# ESPRemote.net
KiCad netlist of a schematic drawn in EAGLE
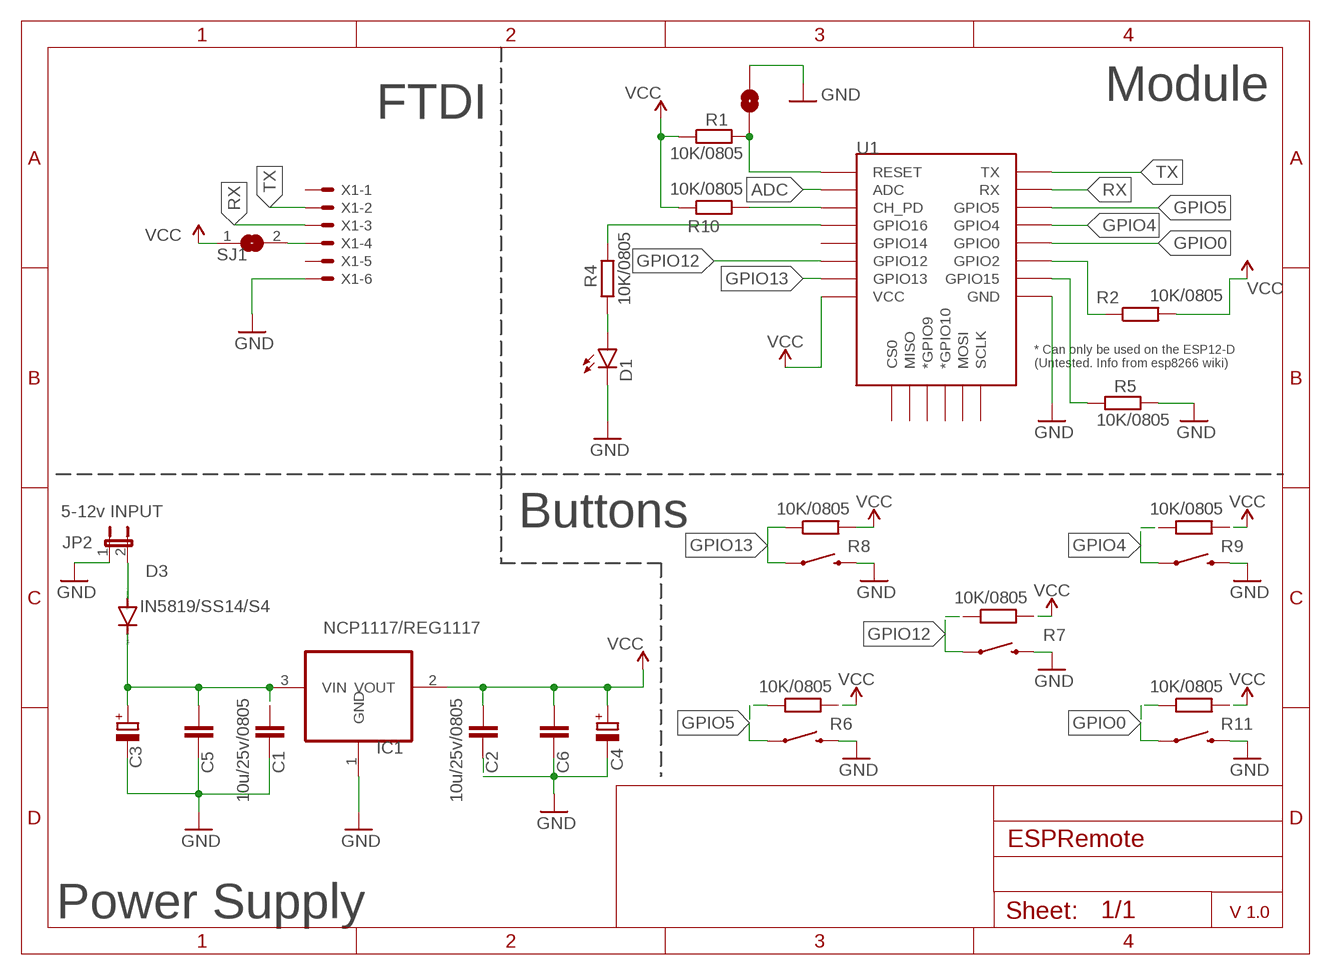
[diagram p0: schematic, sheet 1]

(export (version "E")
  (design (tool "Eeschema 10.0.6"))
  (components
    (comp (ref "C1")
      (value "10u/25v/0805")
      (footprint "eagle-import:C0805")
      (libsource (lib "eagle-import") (part "C-EUC0805"))
    )
    (comp (ref "C2")
      (value "10u/25v/0805")
      (footprint "eagle-import:C0805")
      (libsource (lib "eagle-import") (part "C-EUC0805"))
    )
    (comp (ref "C3")
      (value "CPOL-EUE2-5")
      (footprint "eagle-import:E2-5")
      (libsource (lib "eagle-import") (part "CPOL-EUE2-5"))
    )
    (comp (ref "C4")
      (value "CPOL-EUE2-5")
      (footprint "eagle-import:E2-5")
      (libsource (lib "eagle-import") (part "CPOL-EUE2-5"))
    )
    (comp (ref "C5")
      (value "10u/25v/0805")
      (footprint "eagle-import:C0805")
      (libsource (lib "eagle-import") (part "C-EUC0805"))
    )
    (comp (ref "C6")
      (value "10u/25v/0805")
      (footprint "eagle-import:C0805")
      (libsource (lib "eagle-import") (part "C-EUC0805"))
    )
    (comp (ref "D1")
      (value "BLUE")
      (footprint "eagle-import:CHIP-LED0805")
      (libsource (lib "eagle-import") (part "LEDCHIP-LED0805"))
    )
    (comp (ref "D3")
      (value "IN5819/SS14/S4")
      (footprint "eagle-import:DO-214AC")
      (libsource (lib "eagle-import") (part "DIODE-DO-214AC"))
    )
    (comp (ref "IC1")
      (value "NCP1117/REG1117")
      (footprint "eagle-import:SOT223")
      (fields (field (name "MPN") "REG1117"))
      (libsource (lib "eagle-import") (part "REG1117"))
    )
    (comp (ref "JP1")
      (value "RST")
      (footprint "eagle-import:SMT-JUMPER_2_NO_NO-SILK")
      (libsource (lib "eagle-import") (part "JUMPER-SMT_2_NO_NO-SILK"))
    )
    (comp (ref "JP2")
      (value "5-12v INPUT")
      (footprint "eagle-import:JP1")
      (libsource (lib "eagle-import") (part "JP1E"))
    )
    (comp (ref "R1")
      (value "10K/0805")
      (footprint "eagle-import:R0805")
      (libsource (lib "eagle-import") (part "R-EU_R0805"))
    )
    (comp (ref "R2")
      (value "10K/0805")
      (footprint "eagle-import:R0805")
      (libsource (lib "eagle-import") (part "R-EU_R0805"))
    )
    (comp (ref "R4")
      (value "10K/0805")
      (footprint "eagle-import:R0805")
      (libsource (lib "eagle-import") (part "R-EU_R0805"))
    )
    (comp (ref "R5")
      (value "10K/0805")
      (footprint "eagle-import:R0805")
      (libsource (lib "eagle-import") (part "R-EU_R0805"))
    )
    (comp (ref "R6")
      (value "10K/0805")
      (footprint "eagle-import:R0805")
      (libsource (lib "eagle-import") (part "R-EU_R0805"))
    )
    (comp (ref "R7")
      (value "10K/0805")
      (footprint "eagle-import:R0805")
      (libsource (lib "eagle-import") (part "R-EU_R0805"))
    )
    (comp (ref "R8")
      (value "10K/0805")
      (footprint "eagle-import:R0805")
      (libsource (lib "eagle-import") (part "R-EU_R0805"))
    )
    (comp (ref "R9")
      (value "10K/0805")
      (footprint "eagle-import:R0805")
      (libsource (lib "eagle-import") (part "R-EU_R0805"))
    )
    (comp (ref "R10")
      (value "10K/0805")
      (footprint "eagle-import:R0805")
      (libsource (lib "eagle-import") (part "R-EU_R0805"))
    )
    (comp (ref "R11")
      (value "10K/0805")
      (footprint "eagle-import:R0805")
      (libsource (lib "eagle-import") (part "R-EU_R0805"))
    )
    (comp (ref "S0")
      (value "SMD-SWITCH-6.2MM")
      (footprint "eagle-import:TACTILE_SWITCH_SMD_6.0X3.5MM")
      (libsource (lib "eagle-import") (part "MOMENTARY-SWITCH-SPST-SMD-6.0X3.5MM"))
    )
    (comp (ref "S1")
      (value "SMD-SWITCH-6.2MM")
      (footprint "eagle-import:TACTILE_SWITCH_SMD_6.0X3.5MM")
      (libsource (lib "eagle-import") (part "MOMENTARY-SWITCH-SPST-SMD-6.0X3.5MM"))
    )
    (comp (ref "S2")
      (value "SMD-SWITCH-6.2MM")
      (footprint "eagle-import:TACTILE_SWITCH_SMD_6.0X3.5MM")
      (libsource (lib "eagle-import") (part "MOMENTARY-SWITCH-SPST-SMD-6.0X3.5MM"))
    )
    (comp (ref "S3")
      (value "SMD-SWITCH-6.2MM")
      (footprint "eagle-import:TACTILE_SWITCH_SMD_6.0X3.5MM")
      (libsource (lib "eagle-import") (part "MOMENTARY-SWITCH-SPST-SMD-6.0X3.5MM"))
    )
    (comp (ref "S4")
      (value "SMD-SWITCH-6.2MM")
      (footprint "eagle-import:TACTILE_SWITCH_SMD_6.0X3.5MM")
      (libsource (lib "eagle-import") (part "MOMENTARY-SWITCH-SPST-SMD-6.0X3.5MM"))
    )
    (comp (ref "SJ1") (value "SJ") (footprint "eagle-import:SJ") (libsource (lib "eagle-import") (part "SJ")))
    (comp (ref "U1")
      (value "ESP12ESMD")
      (footprint "eagle-import:ESP12E-SMD")
      (fields (field (name "SPICEPREFIX") "X"))
      (libsource (lib "eagle-import") (part "ESP12ESMD"))
    )
    (comp (ref "X1")
      (value "JST-XH-06-PIN-ROUND-PAD")
      (footprint "eagle-import:JST-XH-06-PACKAGE-ROUND-PAD")
      (libsource (lib "eagle-import") (part "JST-XH-06-PIN-ROUND-PAD"))
    )
  )
  (nets
    (net (code "1") (name "ADC") (class "Default")
      (node (ref "U1") (pin "ADC") (pinfunction "ADC_ADC") (pintype "bidirectional"))
    )
    (net (code "2") (name "GND") (class "Default")
      (node (ref "C1") (pin "1") (pinfunction "1_1") (pintype "passive"))
      (node (ref "C2") (pin "1") (pinfunction "1_1") (pintype "passive"))
      (node (ref "C3") (pin "-") (pinfunction "-_-") (pintype "passive"))
      (node (ref "C4") (pin "-") (pinfunction "-_-") (pintype "passive"))
      (node (ref "C5") (pin "1") (pinfunction "1_1") (pintype "passive"))
      (node (ref "C6") (pin "1") (pinfunction "1_1") (pintype "passive"))
      (node (ref "D1") (pin "C") (pinfunction "C_C") (pintype "passive"))
      (node (ref "IC1") (pin "1") (pinfunction "GND_1") (pintype "power_in"))
      (node (ref "JP1") (pin "2") (pinfunction "2_2") (pintype "passive"))
      (node (ref "JP2") (pin "1") (pinfunction "1_1") (pintype "passive"))
      (node (ref "R5") (pin "2") (pinfunction "2_2") (pintype "passive"))
      (node (ref "S0") (pin "2") (pinfunction "2_2") (pintype "passive"))
      (node (ref "S1") (pin "2") (pinfunction "2_2") (pintype "passive"))
      (node (ref "S2") (pin "2") (pinfunction "2_2") (pintype "passive"))
      (node (ref "S3") (pin "2") (pinfunction "2_2") (pintype "passive"))
      (node (ref "S4") (pin "2") (pinfunction "2_2") (pintype "passive"))
      (node (ref "U1") (pin "GND") (pinfunction "GND_GND") (pintype "bidirectional"))
      (node (ref "X1") (pin "6") (pinfunction "S_6") (pintype "passive"))
    )
    (net (code "3") (name "GPIO0") (class "Default")
      (node (ref "R11") (pin "1") (pinfunction "1_1") (pintype "passive"))
      (node (ref "S4") (pin "1") (pinfunction "1_1") (pintype "passive"))
      (node (ref "U1") (pin "GPIO0") (pinfunction "GPIO0_GPIO0") (pintype "bidirectional"))
    )
    (net (code "4") (name "GPIO4") (class "Default")
      (node (ref "R9") (pin "1") (pinfunction "1_1") (pintype "passive"))
      (node (ref "S3") (pin "1") (pinfunction "1_1") (pintype "passive"))
      (node (ref "U1") (pin "GPIO4") (pinfunction "GPIO4_GPIO4") (pintype "bidirectional"))
    )
    (net (code "5") (name "GPIO5") (class "Default")
      (node (ref "R6") (pin "1") (pinfunction "1_1") (pintype "passive"))
      (node (ref "S2") (pin "1") (pinfunction "1_1") (pintype "passive"))
      (node (ref "U1") (pin "GPIO5") (pinfunction "GPIO5_GPIO5") (pintype "bidirectional"))
    )
    (net (code "6") (name "GPIO12") (class "Default")
      (node (ref "R7") (pin "1") (pinfunction "1_1") (pintype "passive"))
      (node (ref "S1") (pin "1") (pinfunction "1_1") (pintype "passive"))
      (node (ref "U1") (pin "GPIO12") (pinfunction "GPIO12_GPIO12") (pintype "bidirectional"))
    )
    (net (code "7") (name "GPIO13") (class "Default")
      (node (ref "R8") (pin "1") (pinfunction "1_1") (pintype "passive"))
      (node (ref "S0") (pin "1") (pinfunction "1_1") (pintype "passive"))
      (node (ref "U1") (pin "GPIO13") (pinfunction "GPIO13_GPIO13") (pintype "bidirectional"))
    )
    (net (code "8") (name "Net-(D1-PadA)") (class "Default")
      (node (ref "D1") (pin "A") (pinfunction "A_A") (pintype "passive"))
      (node (ref "R4") (pin "1") (pinfunction "1_1") (pintype "passive"))
    )
    (net (code "9") (name "Net-(D3-PadA)") (class "Default")
      (node (ref "D3") (pin "A") (pinfunction "A_A") (pintype "passive"))
      (node (ref "JP2") (pin "2") (pinfunction "2_2") (pintype "passive"))
    )
    (net (code "10") (name "Net-(IC1-VIN)") (class "Default")
      (node (ref "C1") (pin "2") (pinfunction "2_2") (pintype "passive"))
      (node (ref "C3") (pin "+") (pinfunction "+_+") (pintype "passive"))
      (node (ref "C5") (pin "2") (pinfunction "2_2") (pintype "passive"))
      (node (ref "D3") (pin "C") (pinfunction "C_C") (pintype "passive"))
      (node (ref "IC1") (pin "3") (pinfunction "VIN_3") (pintype "input"))
    )
    (net (code "11") (name "Net-(JP1-Pad1)") (class "Default")
      (node (ref "JP1") (pin "1") (pinfunction "1_1") (pintype "passive"))
      (node (ref "R1") (pin "2") (pinfunction "2_2") (pintype "passive"))
      (node (ref "U1") (pin "RESET") (pinfunction "RESET_RESET") (pintype "bidirectional"))
    )
    (net (code "12") (name "Net-(R2-Pad1)") (class "Default")
      (node (ref "R2") (pin "1") (pinfunction "1_1") (pintype "passive"))
      (node (ref "U1") (pin "GPIO2") (pinfunction "GPIO2_GPIO2") (pintype "bidirectional"))
    )
    (net (code "13") (name "Net-(R4-Pad2)") (class "Default")
      (node (ref "R4") (pin "2") (pinfunction "2_2") (pintype "passive"))
      (node (ref "U1") (pin "GPIO16") (pinfunction "GPIO16_GPIO16") (pintype "bidirectional"))
    )
    (net (code "14") (name "Net-(R5-Pad1)") (class "Default")
      (node (ref "R5") (pin "1") (pinfunction "1_1") (pintype "passive"))
      (node (ref "U1") (pin "GPIO15") (pinfunction "GPIO15_GPIO15") (pintype "bidirectional"))
    )
    (net (code "15") (name "Net-(R10-Pad2)") (class "Default")
      (node (ref "R10") (pin "2") (pinfunction "2_2") (pintype "passive"))
      (node (ref "U1") (pin "CH_PD") (pinfunction "CH_PD_CH_PD") (pintype "bidirectional"))
    )
    (net (code "16") (name "Net-(X1D-S)") (class "Default")
      (node (ref "SJ1") (pin "2") (pinfunction "2_2") (pintype "passive"))
      (node (ref "X1") (pin "4") (pinfunction "S_4") (pintype "passive"))
    )
    (net (code "17") (name "RX") (class "Default")
      (node (ref "U1") (pin "RXD0") (pinfunction "RX_RXD0") (pintype "bidirectional"))
      (node (ref "X1") (pin "3") (pinfunction "S_3") (pintype "passive"))
    )
    (net (code "18") (name "TX") (class "Default")
      (node (ref "U1") (pin "TXD0") (pinfunction "TX_TXD0") (pintype "bidirectional"))
      (node (ref "X1") (pin "2") (pinfunction "S_2") (pintype "passive"))
    )
    (net (code "19") (name "VCC") (class "Default")
      (node (ref "C2") (pin "2") (pinfunction "2_2") (pintype "passive"))
      (node (ref "C4") (pin "+") (pinfunction "+_+") (pintype "passive"))
      (node (ref "C6") (pin "2") (pinfunction "2_2") (pintype "passive"))
      (node (ref "IC1") (pin "2") (pinfunction "VOUT_2") (pintype "output"))
      (node (ref "R1") (pin "1") (pinfunction "1_1") (pintype "passive"))
      (node (ref "R10") (pin "1") (pinfunction "1_1") (pintype "passive"))
      (node (ref "R11") (pin "2") (pinfunction "2_2") (pintype "passive"))
      (node (ref "R2") (pin "2") (pinfunction "2_2") (pintype "passive"))
      (node (ref "R6") (pin "2") (pinfunction "2_2") (pintype "passive"))
      (node (ref "R7") (pin "2") (pinfunction "2_2") (pintype "passive"))
      (node (ref "R8") (pin "2") (pinfunction "2_2") (pintype "passive"))
      (node (ref "R9") (pin "2") (pinfunction "2_2") (pintype "passive"))
      (node (ref "SJ1") (pin "1") (pinfunction "1_1") (pintype "passive"))
      (node (ref "U1") (pin "VCC") (pinfunction "VCC_VCC") (pintype "bidirectional"))
    )
    (net (code "20") (name "unconnected-(U1-*GPIO9-PadGPIO9)") (class "Default")
      (node (ref "U1") (pin "GPIO9") (pinfunction "*GPIO9_GPIO9") (pintype "bidirectional"))
    )
    (net (code "21") (name "unconnected-(U1-*GPIO10-PadGPIO10)") (class "Default")
      (node (ref "U1") (pin "GPIO10") (pinfunction "*GPIO10_GPIO10") (pintype "bidirectional"))
    )
    (net (code "22") (name "unconnected-(U1-PadCS0)") (class "Default")
      (node (ref "U1") (pin "CS0") (pinfunction "CS0_CS0") (pintype "bidirectional"))
    )
    (net (code "23") (name "unconnected-(U1-PadGPIO14)") (class "Default")
      (node (ref "U1") (pin "GPIO14") (pinfunction "GPIO14_GPIO14") (pintype "bidirectional"))
    )
    (net (code "24") (name "unconnected-(U1-PadMISO)") (class "Default")
      (node (ref "U1") (pin "MISO") (pinfunction "MISO_MISO") (pintype "bidirectional"))
    )
    (net (code "25") (name "unconnected-(U1-PadMOSI)") (class "Default")
      (node (ref "U1") (pin "MOSI") (pinfunction "MOSI_MOSI") (pintype "bidirectional"))
    )
    (net (code "26") (name "unconnected-(U1-PadSCLK)") (class "Default")
      (node (ref "U1") (pin "SCLK") (pinfunction "SCLK_SCLK") (pintype "bidirectional"))
    )
    (net (code "27") (name "unconnected-(X1A-S-Pad1)") (class "Default")
      (node (ref "X1") (pin "1") (pinfunction "S_1") (pintype "passive"))
    )
    (net (code "28") (name "unconnected-(X1E-S-Pad5)") (class "Default")
      (node (ref "X1") (pin "5") (pinfunction "S_5") (pintype "passive"))
    )
  )
)
